# LAB-04.net
KiCad netlist of a schematic drawn in Altium Designer
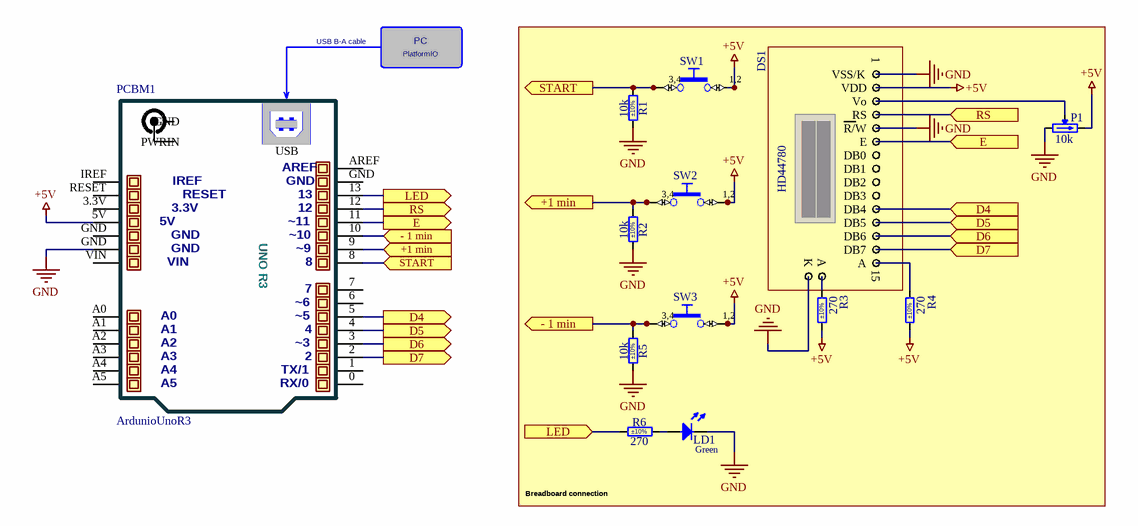
[diagram p0: LAB-04.SchDoc]

(export (version "E")
  (design (tool "Eeschema 10.0.6"))
  (components
    (comp (ref "DS1")
      (value "HD44780")
      (footprint "DS_POWERTIP_PC1202LRS-AWA-B")
      (description "Alphanumeric LCD Display Module, 2 x 12 characters, Dot Size:0.45 x 0.60, Dot Pitch 0.55 x 0.70")
      (fields
        (field (name "PART NUMBER") "DS_POWERTIP_PC1202LRS-AWA-B")
        (field (name "MANUFACTURER") "POWERTIP")
        (field (name "AUTHOR") "CERN DEM JLC")
      )
      (libsource (lib "ICs And Semiconductors") (part "DS_POWERTIP_PC1202"))
    )
    (comp (ref "LD1")
      (value "Green")
      (footprint "LED_DIALIGHT_561-2201-050F")
      (description "LED Green 1C 2A")
      (fields
        (field (name "PART NUMBER") "LED_DIALIGHT_561-2201-050F")
        (field (name "MANUFACTURER") "DIALIGHT")
        (field (name "AUTHOR") "CERN DEM JLC")
      )
      (libsource (lib "ICs And Semiconductors") (part "LED Green 1C 2A"))
    )
    (comp (ref "P1")
      (value "10k")
      (footprint "TRIM_BOURNS_3314G-1")
      (description "Trimming Potentiometer")
      (fields
        (field (name "PART NUMBER") "TRIM_1T_10K_BOURNS_3314G-1-103E")
        (field (name "POWER") "0.25W")
        (field (name "AUTHOR") "CERN DEM JLC")
      )
      (libsource (lib "Resistors") (part "Trimming Potentiometer"))
    )
    (comp (ref "PCBM1")
      (value "ArdunioUnoR3")
      (description "ArdunioUnoR3 Universal SCH Symbol \r\n(C) 230232")
      (libsource (lib "ArduinoUnoR3") (part "ArdunioUnoR3"))
    )
    (comp (ref "R1")
      (value "10k")
      (footprint "RESC3216X65N")
      (description "Resistor - 0.1%")
      (fields
        (field (name "TOLERANCE") "±10%")
        (field (name "PART NUMBER") "R1206_270R_0.1%_0.25W_25PPM")
        (field (name "POWER") "0.25W")
        (field (name "AUTHOR") "CERN DEM JLC")
      )
      (libsource (lib "Resistors") (part "Resistor - 0.1%"))
    )
    (comp (ref "R2")
      (value "10k")
      (footprint "RESC3216X65N")
      (description "Resistor - 0.1%")
      (fields
        (field (name "TOLERANCE") "±10%")
        (field (name "PART NUMBER") "R1206_270R_0.1%_0.25W_25PPM")
        (field (name "POWER") "0.25W")
        (field (name "AUTHOR") "CERN DEM JLC")
      )
      (libsource (lib "Resistors") (part "Resistor - 0.1%"))
    )
    (comp (ref "R3")
      (value "270")
      (footprint "RESC3216X65N")
      (description "Resistor - 0.1%")
      (fields
        (field (name "TOLERANCE") "±10%")
        (field (name "PART NUMBER") "R1206_270R_0.1%_0.25W_25PPM")
        (field (name "POWER") "0.25W")
        (field (name "AUTHOR") "CERN DEM JLC")
      )
      (libsource (lib "Resistors") (part "Resistor - 0.1%"))
    )
    (comp (ref "R4")
      (value "270")
      (footprint "RESC3216X65N")
      (description "Resistor - 0.1%")
      (fields
        (field (name "TOLERANCE") "±10%")
        (field (name "PART NUMBER") "R1206_270R_0.1%_0.25W_25PPM")
        (field (name "POWER") "0.25W")
        (field (name "AUTHOR") "CERN DEM JLC")
      )
      (libsource (lib "Resistors") (part "Resistor - 0.1%"))
    )
    (comp (ref "R5")
      (value "10k")
      (footprint "RESC3216X65N")
      (description "Resistor - 0.1%")
      (fields
        (field (name "TOLERANCE") "±10%")
        (field (name "PART NUMBER") "R1206_270R_0.1%_0.25W_25PPM")
        (field (name "POWER") "0.25W")
        (field (name "AUTHOR") "CERN DEM JLC")
      )
      (libsource (lib "Resistors") (part "Resistor - 0.1%"))
    )
    (comp (ref "R6")
      (value "270")
      (footprint "RESC3216X65N")
      (description "Resistor - 0.1%")
      (fields
        (field (name "TOLERANCE") "±10%")
        (field (name "PART NUMBER") "R1206_270R_0.1%_0.25W_25PPM")
        (field (name "POWER") "0.25W")
        (field (name "AUTHOR") "CERN DEM JLC")
      )
      (libsource (lib "Resistors") (part "Resistor - 0.1%"))
    )
    (comp (ref "SW1")
      (value "Push Button")
      (footprint "PB_ALPS_SKHHDTA010")
      (description "Push-Button Switch SPDT")
      (fields
        (field (name "PART NUMBER") "PB_ALPS_SKHHDTA010")
        (field (name "MANUFACTURER") "ALPS")
        (field (name "AUTHOR") "CERN DEM JLC")
      )
      (libsource (lib "Eletro-mechanical") (part "PB SPST 12NO-34NO"))
    )
    (comp (ref "SW2")
      (value "Push Button")
      (footprint "PB_ALPS_SKHHDTA010")
      (description "Push-Button Switch SPDT")
      (fields
        (field (name "PART NUMBER") "PB_ALPS_SKHHDTA010")
        (field (name "MANUFACTURER") "ALPS")
        (field (name "AUTHOR") "CERN DEM JLC")
      )
      (libsource (lib "Eletro-mechanical") (part "PB SPST 12NO-34NO"))
    )
    (comp (ref "SW3")
      (value "Push Button")
      (footprint "PB_ALPS_SKHHDTA010")
      (description "Push-Button Switch SPDT")
      (fields
        (field (name "PART NUMBER") "PB_ALPS_SKHHDTA010")
        (field (name "MANUFACTURER") "ALPS")
        (field (name "AUTHOR") "CERN DEM JLC")
      )
      (libsource (lib "Eletro-mechanical") (part "PB SPST 12NO-34NO"))
    )
  )
  (nets
    (net (code "1") (name "+5V") (class "Default")
      (node (ref "P1") (pin "3") (pinfunction "CW_3") (pintype "passive"))
      (node (ref "PCBM1") (pin "5V") (pinfunction "5V_5V") (pintype "passive"))
      (node (ref "R3") (pin "2") (pinfunction "2_2") (pintype "passive"))
      (node (ref "R4") (pin "2") (pinfunction "2_2") (pintype "passive"))
      (node (ref "SW1") (pin "1") (pinfunction "1_1") (pintype "bidirectional"))
      (node (ref "SW1") (pin "2") (pinfunction "2_2") (pintype "bidirectional"))
      (node (ref "SW2") (pin "1") (pinfunction "1_1") (pintype "bidirectional"))
      (node (ref "SW2") (pin "2") (pinfunction "2_2") (pintype "bidirectional"))
      (node (ref "SW3") (pin "1") (pinfunction "1_1") (pintype "bidirectional"))
      (node (ref "SW3") (pin "2") (pinfunction "2_2") (pintype "bidirectional"))
    )
    (net (code "2") (name "/+1 min") (class "Default")
      (node (ref "PCBM1") (pin "9") (pinfunction "9_9") (pintype "passive"))
      (node (ref "R2") (pin "2") (pinfunction "2_2") (pintype "passive"))
      (node (ref "SW2") (pin "3") (pinfunction "3_3") (pintype "bidirectional"))
      (node (ref "SW2") (pin "4") (pinfunction "4_4") (pintype "bidirectional"))
    )
    (net (code "3") (name "/- 1 min") (class "Default")
      (node (ref "PCBM1") (pin "10") (pinfunction "10_10") (pintype "passive"))
      (node (ref "R5") (pin "2") (pinfunction "2_2") (pintype "passive"))
      (node (ref "SW3") (pin "3") (pinfunction "3_3") (pintype "bidirectional"))
      (node (ref "SW3") (pin "4") (pinfunction "4_4") (pintype "bidirectional"))
    )
    (net (code "4") (name "/D4") (class "Default")
      (node (ref "PCBM1") (pin "5") (pinfunction "5_5") (pintype "passive"))
    )
    (net (code "5") (name "/D5") (class "Default")
      (node (ref "PCBM1") (pin "4") (pinfunction "4_4") (pintype "passive"))
    )
    (net (code "6") (name "/D6") (class "Default")
      (node (ref "PCBM1") (pin "3") (pinfunction "3_3") (pintype "passive"))
    )
    (net (code "7") (name "/D7") (class "Default")
      (node (ref "PCBM1") (pin "2") (pinfunction "2_2") (pintype "passive"))
    )
    (net (code "8") (name "/E") (class "Default")
      (node (ref "PCBM1") (pin "11") (pinfunction "11_11") (pintype "passive"))
    )
    (net (code "9") (name "/LED") (class "Default")
      (node (ref "PCBM1") (pin "13") (pinfunction "13_13") (pintype "passive"))
      (node (ref "R6") (pin "1") (pinfunction "1_1") (pintype "passive"))
    )
    (net (code "10") (name "/RS") (class "Default")
      (node (ref "PCBM1") (pin "12") (pinfunction "12_12") (pintype "passive"))
    )
    (net (code "11") (name "/START") (class "Default")
      (node (ref "PCBM1") (pin "8") (pinfunction "8_8") (pintype "passive"))
      (node (ref "R1") (pin "2") (pinfunction "2_2") (pintype "passive"))
      (node (ref "SW1") (pin "3") (pinfunction "3_3") (pintype "bidirectional"))
      (node (ref "SW1") (pin "4") (pinfunction "4_4") (pintype "bidirectional"))
    )
    (net (code "12") (name "GND") (class "Default")
      (node (ref "LD1") (pin "1") (pinfunction "C_1") (pintype "passive"))
      (node (ref "P1") (pin "1") (pinfunction "CCW_1") (pintype "passive"))
      (node (ref "PCBM1") (pin "GND") (pinfunction "GND_GND") (pintype "passive"))
      (node (ref "R1") (pin "1") (pinfunction "1_1") (pintype "passive"))
      (node (ref "R2") (pin "1") (pinfunction "1_1") (pintype "passive"))
      (node (ref "R5") (pin "1") (pinfunction "1_1") (pintype "passive"))
    )
    (net (code "13") (name "Net-(LD1-A)") (class "Default")
      (node (ref "LD1") (pin "2") (pinfunction "A_2") (pintype "passive"))
      (node (ref "R6") (pin "2") (pinfunction "2_2") (pintype "passive"))
    )
    (net (code "14") (name "unconnected-(P1-W-Pad2)") (class "Default")
      (node (ref "P1") (pin "2") (pinfunction "W_2") (pintype "passive"))
    )
    (net (code "15") (name "unconnected-(PCBM1-Pad0)") (class "Default")
      (node (ref "PCBM1") (pin "0") (pinfunction "0_0") (pintype "passive"))
    )
    (net (code "16") (name "unconnected-(PCBM1-Pad1)") (class "Default")
      (node (ref "PCBM1") (pin "1") (pinfunction "1_1") (pintype "passive"))
    )
    (net (code "17") (name "unconnected-(PCBM1-Pad3.3V)") (class "Default")
      (node (ref "PCBM1") (pin "3.3V") (pinfunction "3.3V_3.3V") (pintype "passive"))
    )
    (net (code "18") (name "unconnected-(PCBM1-Pad6)") (class "Default")
      (node (ref "PCBM1") (pin "6") (pinfunction "6_6") (pintype "passive"))
    )
    (net (code "19") (name "unconnected-(PCBM1-Pad7)") (class "Default")
      (node (ref "PCBM1") (pin "7") (pinfunction "7_7") (pintype "passive"))
    )
    (net (code "20") (name "unconnected-(PCBM1-PadA0)") (class "Default")
      (node (ref "PCBM1") (pin "A0") (pinfunction "A0_A0") (pintype "passive"))
    )
    (net (code "21") (name "unconnected-(PCBM1-PadA1)") (class "Default")
      (node (ref "PCBM1") (pin "A1") (pinfunction "A1_A1") (pintype "passive"))
    )
    (net (code "22") (name "unconnected-(PCBM1-PadA2)") (class "Default")
      (node (ref "PCBM1") (pin "A2") (pinfunction "A2_A2") (pintype "passive"))
    )
    (net (code "23") (name "unconnected-(PCBM1-PadA3)") (class "Default")
      (node (ref "PCBM1") (pin "A3") (pinfunction "A3_A3") (pintype "passive"))
    )
    (net (code "24") (name "unconnected-(PCBM1-PadA4)") (class "Default")
      (node (ref "PCBM1") (pin "A4") (pinfunction "A4_A4") (pintype "passive"))
    )
    (net (code "25") (name "unconnected-(PCBM1-PadA5)") (class "Default")
      (node (ref "PCBM1") (pin "A5") (pinfunction "A5_A5") (pintype "passive"))
    )
    (net (code "26") (name "unconnected-(PCBM1-PadAREF)") (class "Default")
      (node (ref "PCBM1") (pin "AREF") (pinfunction "AREF_AREF") (pintype "passive"))
    )
    (net (code "27") (name "unconnected-(PCBM1-PadGND)") (class "Default")
      (node (ref "PCBM1") (pin "GND") (pinfunction "GND_GND") (pintype "passive"))
    )
    (net (code "28") (name "unconnected-(PCBM1-PadGND)_1") (class "Default")
      (node (ref "PCBM1") (pin "GND") (pinfunction "GND_GND") (pintype "passive"))
    )
    (net (code "29") (name "unconnected-(PCBM1-PadIREF)") (class "Default")
      (node (ref "PCBM1") (pin "IREF") (pinfunction "IREF_IREF") (pintype "passive"))
    )
    (net (code "30") (name "unconnected-(PCBM1-PadRESET)") (class "Default")
      (node (ref "PCBM1") (pin "RESET") (pinfunction "RESET_RESET") (pintype "passive"))
    )
    (net (code "31") (name "unconnected-(PCBM1-PadVIN)") (class "Default")
      (node (ref "PCBM1") (pin "VIN") (pinfunction "VIN_VIN") (pintype "passive"))
    )
    (net (code "32") (name "unconnected-(R3-Pad1)") (class "Default")
      (node (ref "R3") (pin "1") (pinfunction "1_1") (pintype "passive"))
    )
    (net (code "33") (name "unconnected-(R4-Pad1)") (class "Default")
      (node (ref "R4") (pin "1") (pinfunction "1_1") (pintype "passive"))
    )
  )
)
